# pc_power_on_555.net
KiCad netlist of a schematic drawn in EAGLE
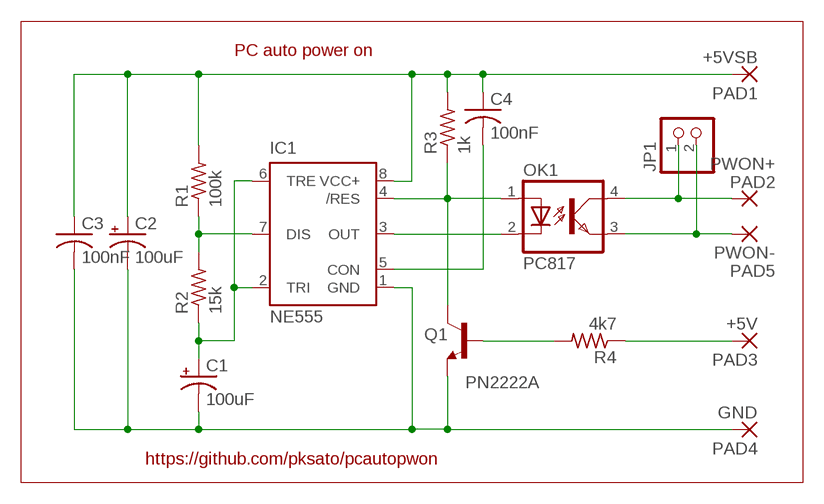
[diagram p0: schematic, sheet 1]

(export (version "E")
  (design (tool "Eeschema 10.0.6"))
  (components
    (comp (ref "C1")
      (value "100uF")
      (footprint "eagle-import:E2,5-7")
      (libsource (lib "eagle-import") (part "CPOL-USE2.5-7"))
    )
    (comp (ref "C2")
      (value "100uF")
      (footprint "eagle-import:E2,5-7")
      (libsource (lib "eagle-import") (part "CPOL-USE2.5-7"))
    )
    (comp (ref "C3")
      (value "100nF")
      (footprint "eagle-import:C025-030X050")
      (libsource (lib "eagle-import") (part "C-US025-030X050"))
    )
    (comp (ref "C4")
      (value "100nF")
      (footprint "eagle-import:C025-030X050")
      (libsource (lib "eagle-import") (part "C-US025-030X050"))
    )
    (comp (ref "IC1")
      (value "NE555")
      (footprint "eagle-import:DIL-08")
      (fields (field (name "MF") "Arrow Electronics") (field (name "MPN") "NE555N"))
      (libsource (lib "eagle-import") (part "NE555"))
    )
    (comp (ref "JP1")
      (value "PINHD-1X2")
      (footprint "eagle-import:1X02")
      (libsource (lib "eagle-import") (part "PINHD-1X2"))
    )
    (comp (ref "OK1")
      (value "PC817")
      (footprint "eagle-import:DIL04")
      (fields (field (name "MPN") "PC817X4J000F"))
      (libsource (lib "eagle-import") (part "PC817"))
    )
    (comp (ref "PAD1")
      (value "+5VSB")
      (footprint "eagle-import:1,6_0,8")
      (libsource (lib "eagle-import") (part "WIREPAD1,6/0,8"))
    )
    (comp (ref "PAD2")
      (value "PWON+")
      (footprint "eagle-import:1,6_0,8")
      (libsource (lib "eagle-import") (part "WIREPAD1,6/0,8"))
    )
    (comp (ref "PAD3")
      (value "+5V")
      (footprint "eagle-import:1,6_0,8")
      (libsource (lib "eagle-import") (part "WIREPAD1,6/0,8"))
    )
    (comp (ref "PAD4")
      (value "GND")
      (footprint "eagle-import:1,6_0,8")
      (libsource (lib "eagle-import") (part "WIREPAD1,6/0,8"))
    )
    (comp (ref "PAD5")
      (value "PWON-")
      (footprint "eagle-import:1,6_0,8")
      (libsource (lib "eagle-import") (part "WIREPAD1,6/0,8"))
    )
    (comp (ref "Q1")
      (value "PN2222A")
      (footprint "eagle-import:TO92-EBC")
      (libsource (lib "eagle-import") (part "-NPN-TO92-EBC2N2222"))
    )
    (comp (ref "R1")
      (value "100k")
      (footprint "eagle-import:0207_10")
      (libsource (lib "eagle-import") (part "R-US_0207/10"))
    )
    (comp (ref "R2")
      (value "15k")
      (footprint "eagle-import:0207_10")
      (libsource (lib "eagle-import") (part "R-US_0207/10"))
    )
    (comp (ref "R3")
      (value "1k")
      (footprint "eagle-import:0207_10")
      (libsource (lib "eagle-import") (part "R-US_0207/10"))
    )
    (comp (ref "R4")
      (value "4k7")
      (footprint "eagle-import:0207_10")
      (libsource (lib "eagle-import") (part "R-US_0207/10"))
    )
  )
  (nets
    (net (code "1") (name "Net-(IC1-CON)") (class "Default")
      (node (ref "C4") (pin "2") (pinfunction "2_2") (pintype "passive"))
      (node (ref "IC1") (pin "5") (pinfunction "CON_5") (pintype "input"))
    )
    (net (code "2") (name "Net-(IC1-DIS)") (class "Default")
      (node (ref "IC1") (pin "7") (pinfunction "DIS_7") (pintype "input"))
      (node (ref "R1") (pin "1") (pinfunction "1_1") (pintype "passive"))
      (node (ref "R2") (pin "2") (pinfunction "2_2") (pintype "passive"))
    )
    (net (code "3") (name "Net-(IC1-GND)") (class "Default")
      (node (ref "C1") (pin "-") (pinfunction "-_-") (pintype "passive"))
      (node (ref "C2") (pin "-") (pinfunction "-_-") (pintype "passive"))
      (node (ref "C3") (pin "2") (pinfunction "2_2") (pintype "passive"))
      (node (ref "IC1") (pin "1") (pinfunction "GND_1") (pintype "power_in"))
      (node (ref "PAD4") (pin "1") (pinfunction "P_1") (pintype "passive"))
      (node (ref "Q1") (pin "E") (pinfunction "E_E") (pintype "passive"))
    )
    (net (code "4") (name "Net-(IC1-OUT)") (class "Default")
      (node (ref "IC1") (pin "3") (pinfunction "OUT_3") (pintype "output"))
      (node (ref "OK1") (pin "2") (pinfunction "C_2") (pintype "passive"))
    )
    (net (code "5") (name "Net-(IC1-TRE)") (class "Default")
      (node (ref "C1") (pin "+") (pinfunction "+_+") (pintype "passive"))
      (node (ref "IC1") (pin "2") (pinfunction "TRI_2") (pintype "input"))
      (node (ref "IC1") (pin "6") (pinfunction "TRE_6") (pintype "input"))
      (node (ref "R2") (pin "1") (pinfunction "1_1") (pintype "passive"))
    )
    (net (code "6") (name "Net-(IC1-VCC+)") (class "Default")
      (node (ref "C2") (pin "+") (pinfunction "+_+") (pintype "passive"))
      (node (ref "C3") (pin "1") (pinfunction "1_1") (pintype "passive"))
      (node (ref "C4") (pin "1") (pinfunction "1_1") (pintype "passive"))
      (node (ref "IC1") (pin "8") (pinfunction "VCC+_8") (pintype "power_in"))
      (node (ref "PAD1") (pin "1") (pinfunction "P_1") (pintype "passive"))
      (node (ref "R1") (pin "2") (pinfunction "2_2") (pintype "passive"))
      (node (ref "R3") (pin "2") (pinfunction "2_2") (pintype "passive"))
    )
    (net (code "7") (name "Net-(IC1-{slash}RES)") (class "Default")
      (node (ref "IC1") (pin "4") (pinfunction "/RES_4") (pintype "input"))
      (node (ref "OK1") (pin "1") (pinfunction "A_1") (pintype "passive"))
      (node (ref "Q1") (pin "C") (pinfunction "C_C") (pintype "passive"))
      (node (ref "R3") (pin "1") (pinfunction "1_1") (pintype "passive"))
    )
    (net (code "8") (name "Net-(OK1-COL)") (class "Default")
      (node (ref "JP1") (pin "1") (pinfunction "1_1") (pintype "passive"))
      (node (ref "OK1") (pin "4") (pinfunction "COL_4") (pintype "passive"))
      (node (ref "PAD2") (pin "1") (pinfunction "P_1") (pintype "passive"))
    )
    (net (code "9") (name "Net-(OK1-EMIT)") (class "Default")
      (node (ref "JP1") (pin "2") (pinfunction "2_2") (pintype "passive"))
      (node (ref "OK1") (pin "3") (pinfunction "EMIT_3") (pintype "passive"))
      (node (ref "PAD5") (pin "1") (pinfunction "P_1") (pintype "passive"))
    )
    (net (code "10") (name "Net-(PAD3-P)") (class "Default")
      (node (ref "PAD3") (pin "1") (pinfunction "P_1") (pintype "passive"))
      (node (ref "R4") (pin "1") (pinfunction "1_1") (pintype "passive"))
    )
    (net (code "11") (name "Net-(Q1-PadB)") (class "Default")
      (node (ref "Q1") (pin "B") (pinfunction "B_B") (pintype "passive"))
      (node (ref "R4") (pin "2") (pinfunction "2_2") (pintype "passive"))
    )
  )
)
